# lcd-power-distribution.net
KiCad netlist of a schematic drawn in EAGLE
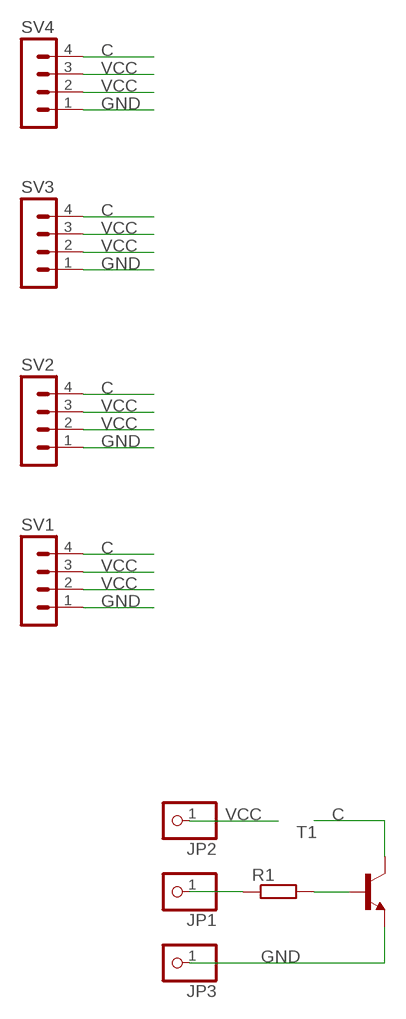
[diagram p0: schematic, sheet 1]

(export (version "E")
  (design (tool "Eeschema 10.0.6"))
  (components
    (comp (ref "JP1")
      (value "PINHD-1X1")
      (footprint "eagle-import:1X01")
      (libsource (lib "eagle-import") (part "PINHD-1X1"))
    )
    (comp (ref "JP2")
      (value "PINHD-1X1")
      (footprint "eagle-import:1X01")
      (libsource (lib "eagle-import") (part "PINHD-1X1"))
    )
    (comp (ref "JP3")
      (value "PINHD-1X1")
      (footprint "eagle-import:1X01")
      (libsource (lib "eagle-import") (part "PINHD-1X1"))
    )
    (comp (ref "R1")
      (value "R-EU_0207/7")
      (footprint "eagle-import:0207_7")
      (libsource (lib "eagle-import") (part "R-EU_0207/7"))
    )
    (comp (ref "SV1")
      (value "MA04-1")
      (footprint "eagle-import:MA04-1")
      (libsource (lib "eagle-import") (part "MA04-1"))
    )
    (comp (ref "SV2")
      (value "MA04-1")
      (footprint "eagle-import:MA04-1")
      (libsource (lib "eagle-import") (part "MA04-1"))
    )
    (comp (ref "SV3")
      (value "MA04-1")
      (footprint "eagle-import:MA04-1")
      (libsource (lib "eagle-import") (part "MA04-1"))
    )
    (comp (ref "SV4")
      (value "MA04-1")
      (footprint "eagle-import:MA04-1")
      (libsource (lib "eagle-import") (part "MA04-1"))
    )
    (comp (ref "T1")
      (value "2N3904-NPN-TO92-EBC")
      (footprint "eagle-import:TO92-EBC")
      (libsource (lib "eagle-import") (part "-NPN-TO92-EBC2N3904"))
    )
  )
  (nets
    (net (code "1") (name "/C") (class "Default")
      (node (ref "SV1") (pin "4") (pinfunction "4_4") (pintype "passive"))
      (node (ref "SV2") (pin "4") (pinfunction "4_4") (pintype "passive"))
      (node (ref "SV3") (pin "4") (pinfunction "4_4") (pintype "passive"))
      (node (ref "SV4") (pin "4") (pinfunction "4_4") (pintype "passive"))
      (node (ref "T1") (pin "C") (pinfunction "C_C") (pintype "passive"))
    )
    (net (code "2") (name "/GND") (class "Default")
      (node (ref "JP3") (pin "1") (pinfunction "1_1") (pintype "passive"))
      (node (ref "SV1") (pin "1") (pinfunction "1_1") (pintype "passive"))
      (node (ref "SV2") (pin "1") (pinfunction "1_1") (pintype "passive"))
      (node (ref "SV3") (pin "1") (pinfunction "1_1") (pintype "passive"))
      (node (ref "SV4") (pin "1") (pinfunction "1_1") (pintype "passive"))
      (node (ref "T1") (pin "E") (pinfunction "E_E") (pintype "passive"))
    )
    (net (code "3") (name "/VCC") (class "Default")
      (node (ref "JP2") (pin "1") (pinfunction "1_1") (pintype "passive"))
      (node (ref "SV1") (pin "2") (pinfunction "2_2") (pintype "passive"))
      (node (ref "SV1") (pin "3") (pinfunction "3_3") (pintype "passive"))
      (node (ref "SV2") (pin "2") (pinfunction "2_2") (pintype "passive"))
      (node (ref "SV2") (pin "3") (pinfunction "3_3") (pintype "passive"))
      (node (ref "SV3") (pin "2") (pinfunction "2_2") (pintype "passive"))
      (node (ref "SV3") (pin "3") (pinfunction "3_3") (pintype "passive"))
      (node (ref "SV4") (pin "2") (pinfunction "2_2") (pintype "passive"))
      (node (ref "SV4") (pin "3") (pinfunction "3_3") (pintype "passive"))
    )
    (net (code "4") (name "Net-(JP1-Pad1)") (class "Default")
      (node (ref "JP1") (pin "1") (pinfunction "1_1") (pintype "passive"))
      (node (ref "R1") (pin "1") (pinfunction "1_1") (pintype "passive"))
    )
    (net (code "5") (name "Net-(R1-Pad2)") (class "Default")
      (node (ref "R1") (pin "2") (pinfunction "2_2") (pintype "passive"))
      (node (ref "T1") (pin "B") (pinfunction "B_B") (pintype "passive"))
    )
  )
)
